# Nixie_breakout_v1_0.net
KiCad netlist of a schematic drawn in EAGLE
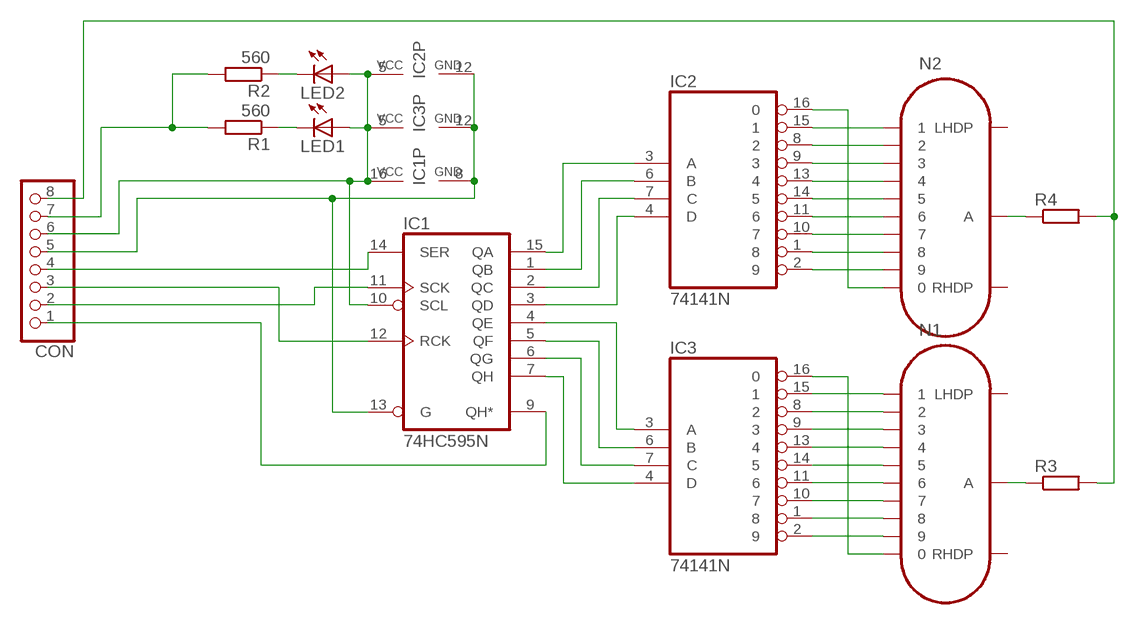
[diagram p0: schematic, sheet 1]

(export (version "E")
  (design (tool "Eeschema 10.0.6"))
  (components
    (comp (ref "CON")
      (value "PINHD-1X8")
      (footprint "eagle-import:1X08")
      (libsource (lib "eagle-import") (part "PINHD-1X8"))
    )
    (comp (ref "IC1")
      (value "74HC595N")
      (footprint "eagle-import:DIL16")
      (libsource (lib "eagle-import") (part "74595NHC"))
    )
    (comp (ref "IC2")
      (value "74141N")
      (footprint "eagle-import:DIL16")
      (libsource (lib "eagle-import") (part "74141N"))
    )
    (comp (ref "IC3")
      (value "74141N")
      (footprint "eagle-import:DIL16")
      (libsource (lib "eagle-import") (part "74141N"))
    )
    (comp (ref "LED1")
      (value "LED3MM")
      (footprint "eagle-import:LED3MM")
      (libsource (lib "eagle-import") (part "LED3MM"))
    )
    (comp (ref "LED2")
      (value "LED3MM")
      (footprint "eagle-import:LED3MM")
      (libsource (lib "eagle-import") (part "LED3MM"))
    )
    (comp (ref "N1")
      (value "IN-14")
      (footprint "eagle-import:IN-14")
      (libsource (lib "eagle-import") (part "IN-14"))
    )
    (comp (ref "N2")
      (value "IN-14")
      (footprint "eagle-import:IN-14")
      (libsource (lib "eagle-import") (part "IN-14"))
    )
    (comp (ref "R1")
      (value "560")
      (footprint "eagle-import:0204_7")
      (libsource (lib "eagle-import") (part "R-EU_0204/7"))
    )
    (comp (ref "R2")
      (value "560")
      (footprint "eagle-import:0204_7")
      (libsource (lib "eagle-import") (part "R-EU_0204/7"))
    )
    (comp (ref "R3")
      (value "R-EU_0204/7")
      (footprint "eagle-import:0204_7")
      (libsource (lib "eagle-import") (part "R-EU_0204/7"))
    )
    (comp (ref "R4")
      (value "R-EU_0204/7")
      (footprint "eagle-import:0204_7")
      (libsource (lib "eagle-import") (part "R-EU_0204/7"))
    )
  )
  (nets
    (net (code "1") (name "Net-(CON-Pad7)") (class "Default")
      (node (ref "CON") (pin "7") (pinfunction "7_7") (pintype "passive"))
      (node (ref "R1") (pin "2") (pinfunction "2_2") (pintype "passive"))
      (node (ref "R2") (pin "2") (pinfunction "2_2") (pintype "passive"))
    )
    (net (code "2") (name "Net-(CON-Pad8)") (class "Default")
      (node (ref "CON") (pin "8") (pinfunction "8_8") (pintype "passive"))
      (node (ref "R3") (pin "2") (pinfunction "2_2") (pintype "passive"))
      (node (ref "R4") (pin "2") (pinfunction "2_2") (pintype "passive"))
    )
    (net (code "3") (name "Net-(IC1A-G)") (class "Default")
      (node (ref "CON") (pin "5") (pinfunction "5_5") (pintype "passive"))
      (node (ref "IC1") (pin "13") (pinfunction "G_13") (pintype "input"))
      (node (ref "IC1") (pin "8") (pinfunction "GND_8") (pintype "power_in"))
      (node (ref "IC2") (pin "12") (pinfunction "GND_12") (pintype "power_in"))
      (node (ref "IC3") (pin "12") (pinfunction "GND_12") (pintype "power_in"))
    )
    (net (code "4") (name "Net-(IC1A-QA)") (class "Default")
      (node (ref "IC1") (pin "15") (pinfunction "QA_15") (pintype "tri_state"))
      (node (ref "IC2") (pin "3") (pinfunction "A_3") (pintype "input"))
    )
    (net (code "5") (name "Net-(IC1A-QB)") (class "Default")
      (node (ref "IC1") (pin "1") (pinfunction "QB_1") (pintype "tri_state"))
      (node (ref "IC2") (pin "6") (pinfunction "B_6") (pintype "input"))
    )
    (net (code "6") (name "Net-(IC1A-QC)") (class "Default")
      (node (ref "IC1") (pin "2") (pinfunction "QC_2") (pintype "tri_state"))
      (node (ref "IC2") (pin "7") (pinfunction "C_7") (pintype "input"))
    )
    (net (code "7") (name "Net-(IC1A-QD)") (class "Default")
      (node (ref "IC1") (pin "3") (pinfunction "QD_3") (pintype "tri_state"))
      (node (ref "IC2") (pin "4") (pinfunction "D_4") (pintype "input"))
    )
    (net (code "8") (name "Net-(IC1A-QE)") (class "Default")
      (node (ref "IC1") (pin "4") (pinfunction "QE_4") (pintype "tri_state"))
      (node (ref "IC3") (pin "3") (pinfunction "A_3") (pintype "input"))
    )
    (net (code "9") (name "Net-(IC1A-QF)") (class "Default")
      (node (ref "IC1") (pin "5") (pinfunction "QF_5") (pintype "tri_state"))
      (node (ref "IC3") (pin "6") (pinfunction "B_6") (pintype "input"))
    )
    (net (code "10") (name "Net-(IC1A-QG)") (class "Default")
      (node (ref "IC1") (pin "6") (pinfunction "QG_6") (pintype "tri_state"))
      (node (ref "IC3") (pin "7") (pinfunction "C_7") (pintype "input"))
    )
    (net (code "11") (name "Net-(IC1A-QH)") (class "Default")
      (node (ref "IC1") (pin "7") (pinfunction "QH_7") (pintype "tri_state"))
      (node (ref "IC3") (pin "4") (pinfunction "D_4") (pintype "input"))
    )
    (net (code "12") (name "Net-(IC1A-QH*)") (class "Default")
      (node (ref "CON") (pin "1") (pinfunction "1_1") (pintype "passive"))
      (node (ref "IC1") (pin "9") (pinfunction "QH*_9") (pintype "tri_state"))
    )
    (net (code "13") (name "Net-(IC1A-RCK)") (class "Default")
      (node (ref "CON") (pin "3") (pinfunction "3_3") (pintype "passive"))
      (node (ref "IC1") (pin "12") (pinfunction "RCK_12") (pintype "input"))
    )
    (net (code "14") (name "Net-(IC1A-SCK)") (class "Default")
      (node (ref "CON") (pin "2") (pinfunction "2_2") (pintype "passive"))
      (node (ref "IC1") (pin "11") (pinfunction "SCK_11") (pintype "input"))
    )
    (net (code "15") (name "Net-(IC1A-SCL)") (class "Default")
      (node (ref "CON") (pin "6") (pinfunction "6_6") (pintype "passive"))
      (node (ref "IC1") (pin "10") (pinfunction "SCL_10") (pintype "input"))
      (node (ref "IC1") (pin "16") (pinfunction "VCC_16") (pintype "power_in"))
      (node (ref "IC2") (pin "5") (pinfunction "VCC_5") (pintype "power_in"))
      (node (ref "IC3") (pin "5") (pinfunction "VCC_5") (pintype "power_in"))
      (node (ref "LED1") (pin "A") (pinfunction "A_A") (pintype "passive"))
      (node (ref "LED2") (pin "A") (pinfunction "A_A") (pintype "passive"))
    )
    (net (code "16") (name "Net-(IC1A-SER)") (class "Default")
      (node (ref "CON") (pin "4") (pinfunction "4_4") (pintype "passive"))
      (node (ref "IC1") (pin "14") (pinfunction "SER_14") (pintype "input"))
    )
    (net (code "17") (name "Net-(IC2A-0)") (class "Default")
      (node (ref "IC2") (pin "16") (pinfunction "0_16") (pintype "open_collector"))
      (node (ref "N2") (pin "0") (pinfunction "0_0") (pintype "bidirectional"))
    )
    (net (code "18") (name "Net-(IC2A-1)") (class "Default")
      (node (ref "IC2") (pin "15") (pinfunction "1_15") (pintype "open_collector"))
      (node (ref "N2") (pin "1") (pinfunction "1_1") (pintype "bidirectional"))
    )
    (net (code "19") (name "Net-(IC2A-2)") (class "Default")
      (node (ref "IC2") (pin "8") (pinfunction "2_8") (pintype "open_collector"))
      (node (ref "N2") (pin "2") (pinfunction "2_2") (pintype "bidirectional"))
    )
    (net (code "20") (name "Net-(IC2A-3)") (class "Default")
      (node (ref "IC2") (pin "9") (pinfunction "3_9") (pintype "open_collector"))
      (node (ref "N2") (pin "3") (pinfunction "3_3") (pintype "bidirectional"))
    )
    (net (code "21") (name "Net-(IC2A-4)") (class "Default")
      (node (ref "IC2") (pin "13") (pinfunction "4_13") (pintype "open_collector"))
      (node (ref "N2") (pin "4") (pinfunction "4_4") (pintype "bidirectional"))
    )
    (net (code "22") (name "Net-(IC2A-5)") (class "Default")
      (node (ref "IC2") (pin "14") (pinfunction "5_14") (pintype "open_collector"))
      (node (ref "N2") (pin "5") (pinfunction "5_5") (pintype "bidirectional"))
    )
    (net (code "23") (name "Net-(IC2A-6)") (class "Default")
      (node (ref "IC2") (pin "11") (pinfunction "6_11") (pintype "open_collector"))
      (node (ref "N2") (pin "6") (pinfunction "6_6") (pintype "bidirectional"))
    )
    (net (code "24") (name "Net-(IC2A-7)") (class "Default")
      (node (ref "IC2") (pin "10") (pinfunction "7_10") (pintype "open_collector"))
      (node (ref "N2") (pin "7") (pinfunction "7_7") (pintype "bidirectional"))
    )
    (net (code "25") (name "Net-(IC2A-8)") (class "Default")
      (node (ref "IC2") (pin "1") (pinfunction "8_1") (pintype "open_collector"))
      (node (ref "N2") (pin "8") (pinfunction "8_8") (pintype "bidirectional"))
    )
    (net (code "26") (name "Net-(IC2A-9)") (class "Default")
      (node (ref "IC2") (pin "2") (pinfunction "9_2") (pintype "open_collector"))
      (node (ref "N2") (pin "9") (pinfunction "9_9") (pintype "bidirectional"))
    )
    (net (code "27") (name "Net-(IC3A-0)") (class "Default")
      (node (ref "IC3") (pin "16") (pinfunction "0_16") (pintype "open_collector"))
      (node (ref "N1") (pin "0") (pinfunction "0_0") (pintype "bidirectional"))
    )
    (net (code "28") (name "Net-(IC3A-1)") (class "Default")
      (node (ref "IC3") (pin "15") (pinfunction "1_15") (pintype "open_collector"))
      (node (ref "N1") (pin "1") (pinfunction "1_1") (pintype "bidirectional"))
    )
    (net (code "29") (name "Net-(IC3A-2)") (class "Default")
      (node (ref "IC3") (pin "8") (pinfunction "2_8") (pintype "open_collector"))
      (node (ref "N1") (pin "2") (pinfunction "2_2") (pintype "bidirectional"))
    )
    (net (code "30") (name "Net-(IC3A-3)") (class "Default")
      (node (ref "IC3") (pin "9") (pinfunction "3_9") (pintype "open_collector"))
      (node (ref "N1") (pin "3") (pinfunction "3_3") (pintype "bidirectional"))
    )
    (net (code "31") (name "Net-(IC3A-4)") (class "Default")
      (node (ref "IC3") (pin "13") (pinfunction "4_13") (pintype "open_collector"))
      (node (ref "N1") (pin "4") (pinfunction "4_4") (pintype "bidirectional"))
    )
    (net (code "32") (name "Net-(IC3A-5)") (class "Default")
      (node (ref "IC3") (pin "14") (pinfunction "5_14") (pintype "open_collector"))
      (node (ref "N1") (pin "5") (pinfunction "5_5") (pintype "bidirectional"))
    )
    (net (code "33") (name "Net-(IC3A-6)") (class "Default")
      (node (ref "IC3") (pin "11") (pinfunction "6_11") (pintype "open_collector"))
      (node (ref "N1") (pin "6") (pinfunction "6_6") (pintype "bidirectional"))
    )
    (net (code "34") (name "Net-(IC3A-7)") (class "Default")
      (node (ref "IC3") (pin "10") (pinfunction "7_10") (pintype "open_collector"))
      (node (ref "N1") (pin "7") (pinfunction "7_7") (pintype "bidirectional"))
    )
    (net (code "35") (name "Net-(IC3A-8)") (class "Default")
      (node (ref "IC3") (pin "1") (pinfunction "8_1") (pintype "open_collector"))
      (node (ref "N1") (pin "8") (pinfunction "8_8") (pintype "bidirectional"))
    )
    (net (code "36") (name "Net-(IC3A-9)") (class "Default")
      (node (ref "IC3") (pin "2") (pinfunction "9_2") (pintype "open_collector"))
      (node (ref "N1") (pin "9") (pinfunction "9_9") (pintype "bidirectional"))
    )
    (net (code "37") (name "Net-(LED1-C)") (class "Default")
      (node (ref "LED1") (pin "K") (pinfunction "C_K") (pintype "passive"))
      (node (ref "R1") (pin "1") (pinfunction "1_1") (pintype "passive"))
    )
    (net (code "38") (name "Net-(LED2-C)") (class "Default")
      (node (ref "LED2") (pin "K") (pinfunction "C_K") (pintype "passive"))
      (node (ref "R2") (pin "1") (pinfunction "1_1") (pintype "passive"))
    )
    (net (code "39") (name "Net-(N1-PadA)") (class "Default")
      (node (ref "N1") (pin "A") (pinfunction "A_A") (pintype "bidirectional"))
      (node (ref "R3") (pin "1") (pinfunction "1_1") (pintype "passive"))
    )
    (net (code "40") (name "Net-(N2-PadA)") (class "Default")
      (node (ref "N2") (pin "A") (pinfunction "A_A") (pintype "bidirectional"))
      (node (ref "R4") (pin "1") (pinfunction "1_1") (pintype "passive"))
    )
    (net (code "41") (name "unconnected-(N1-PadLHDP)") (class "Default")
      (node (ref "N1") (pin "LHDP") (pinfunction "LHDP_LHDP") (pintype "bidirectional"))
    )
    (net (code "42") (name "unconnected-(N1-PadRHDP)") (class "Default")
      (node (ref "N1") (pin "RHDP") (pinfunction "RHDP_RHDP") (pintype "bidirectional"))
    )
    (net (code "43") (name "unconnected-(N2-PadLHDP)") (class "Default")
      (node (ref "N2") (pin "LHDP") (pinfunction "LHDP_LHDP") (pintype "bidirectional"))
    )
    (net (code "44") (name "unconnected-(N2-PadRHDP)") (class "Default")
      (node (ref "N2") (pin "RHDP") (pinfunction "RHDP_RHDP") (pintype "bidirectional"))
    )
  )
)
